# QCopterFC_EXTERN_Sch.net
KiCad netlist of a schematic drawn in Altium Designer
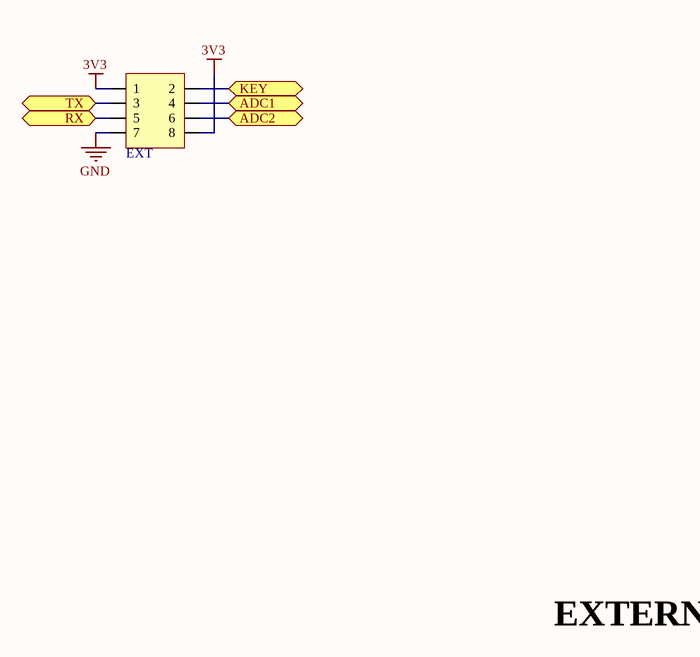
[diagram p0: QCopterFC_EXTERN_Sch.SchDoc]

(export (version "E")
  (design (tool "Eeschema 10.0.6"))
  (components
    (comp (ref "EXT")
      (value "HDR2X4_90_2.54")
      (footprint "PCB_Connector:HDR2X4_90_2.54")
      (description "Header")
      (libsource (lib "SCH_Connector") (part "HDR2X4_90_2.54"))
    )
  )
  (nets
    (net (code "1") (name "/ADC1") (class "Default")
      (node (ref "EXT") (pin "4") (pinfunction "4_4") (pintype "passive"))
    )
    (net (code "2") (name "/ADC2") (class "Default")
      (node (ref "EXT") (pin "6") (pinfunction "6_6") (pintype "passive"))
    )
    (net (code "4") (name "/KEY") (class "Default")
      (node (ref "EXT") (pin "2") (pinfunction "2_2") (pintype "passive"))
    )
    (net (code "5") (name "/RX") (class "Default")
      (node (ref "EXT") (pin "5") (pinfunction "5_5") (pintype "passive"))
    )
    (net (code "6") (name "/TX") (class "Default")
      (node (ref "EXT") (pin "3") (pinfunction "3_3") (pintype "passive"))
    )
    (net (code "7") (name "3V3") (class "Default")
      (node (ref "EXT") (pin "1") (pinfunction "1_1") (pintype "passive"))
      (node (ref "EXT") (pin "8") (pinfunction "8_8") (pintype "passive"))
    )
    (net (code "8") (name "GND") (class "Default")
      (node (ref "EXT") (pin "7") (pinfunction "7_7") (pintype "passive"))
    )
  )
)
